# main_module.net
KiCad netlist of a schematic drawn in EAGLE
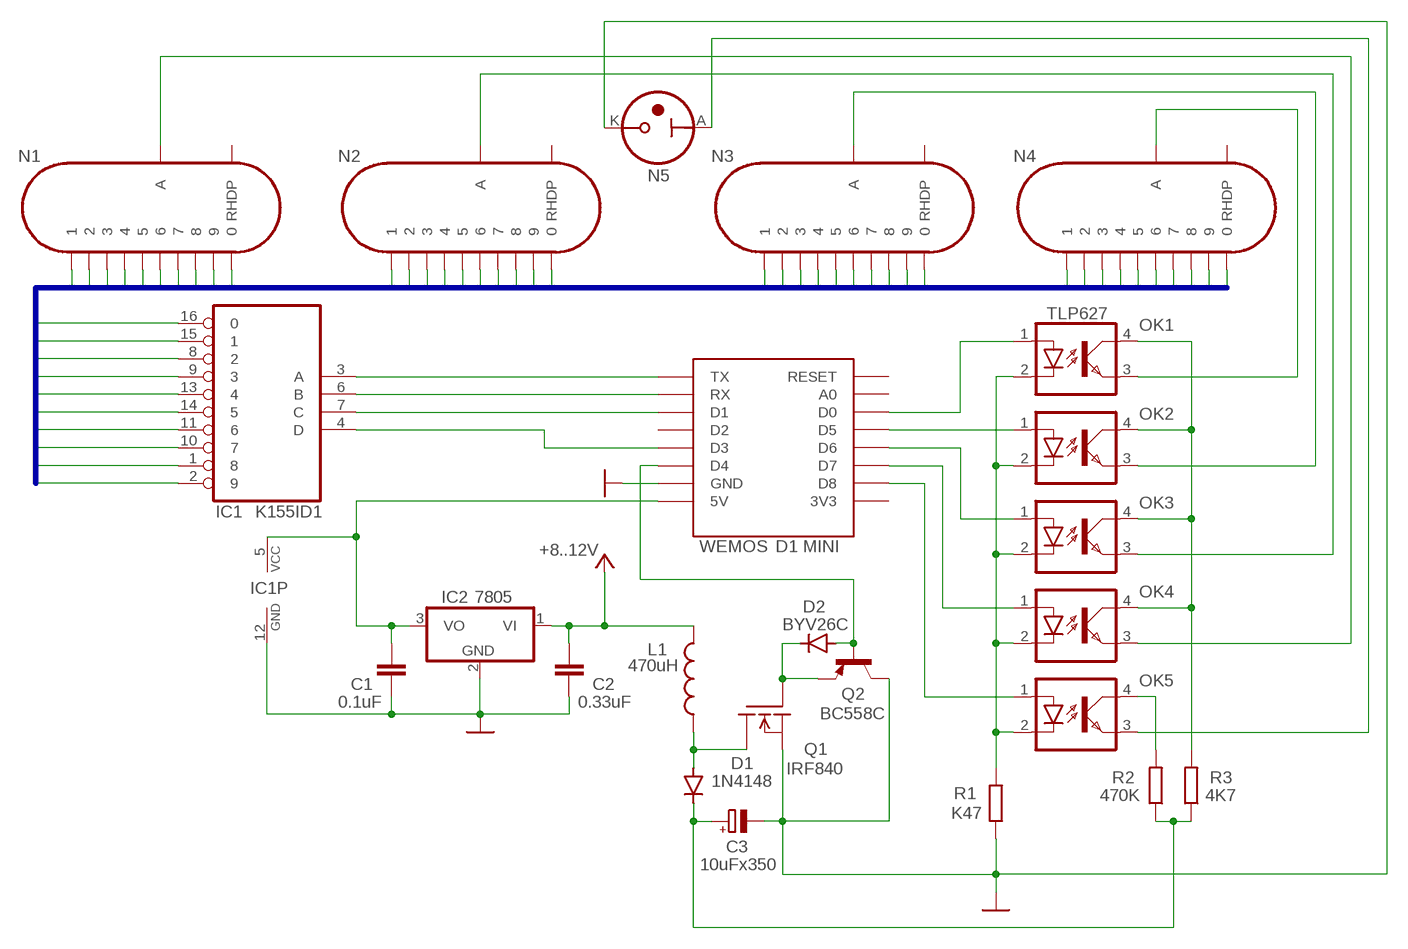
[diagram p0: schematic, sheet 1]

(export (version "E")
  (design (tool "Eeschema 10.0.6"))
  (components
    (comp (ref "C1")
      (value "0.1uF")
      (footprint "eagle-import:C075-052X106")
      (libsource (lib "eagle-import") (part "C-EU075-052X106"))
    )
    (comp (ref "C2")
      (value "0.33uF")
      (footprint "eagle-import:C075-052X106")
      (libsource (lib "eagle-import") (part "C-EU075-052X106"))
    )
    (comp (ref "C3")
      (value "10uFx350")
      (footprint "eagle-import:E5-10,5")
      (libsource (lib "eagle-import") (part "CPOL-EUE5-10.5"))
    )
    (comp (ref "D1")
      (value "1N4148")
      (footprint "eagle-import:DO35-10")
      (libsource (lib "eagle-import") (part "1N4148DO35-10"))
    )
    (comp (ref "D2")
      (value "BYV26C")
      (footprint "eagle-import:SOD57-10")
      (libsource (lib "eagle-import") (part "BYV27"))
    )
    (comp (ref "IC1")
      (value "K155ID1")
      (footprint "eagle-import:DIL16")
      (libsource (lib "eagle-import") (part "74141N"))
    )
    (comp (ref "IC2")
      (value "7805")
      (footprint "eagle-import:TO220H")
      (libsource (lib "eagle-import") (part "78T05"))
    )
    (comp (ref "L1")
      (value "470uH")
      (footprint "eagle-import:6000-XXXX-RC")
      (libsource (lib "eagle-import") (part "L-US6000-XXX-RC"))
    )
    (comp (ref "N1")
      (value "IN-8-2")
      (footprint "eagle-import:IN-8-2")
      (libsource (lib "eagle-import") (part "IN-8-2"))
    )
    (comp (ref "N2")
      (value "IN-8-2")
      (footprint "eagle-import:IN-8-2")
      (libsource (lib "eagle-import") (part "IN-8-2"))
    )
    (comp (ref "N3")
      (value "IN-8-2")
      (footprint "eagle-import:IN-8-2")
      (libsource (lib "eagle-import") (part "IN-8-2"))
    )
    (comp (ref "N4")
      (value "IN-8-2")
      (footprint "eagle-import:IN-8-2")
      (libsource (lib "eagle-import") (part "IN-8-2"))
    )
    (comp (ref "N5")
      (value "IN-3")
      (footprint "eagle-import:IN-3")
      (libsource (lib "eagle-import") (part "IN-3"))
    )
    (comp (ref "OK1")
      (value "TLP627")
      (footprint "eagle-import:DIL04")
      (libsource (lib "eagle-import") (part "LTV816"))
    )
    (comp (ref "OK2")
      (value "LTV816")
      (footprint "eagle-import:DIL04")
      (libsource (lib "eagle-import") (part "LTV816"))
    )
    (comp (ref "OK3")
      (value "LTV816")
      (footprint "eagle-import:DIL04")
      (libsource (lib "eagle-import") (part "LTV816"))
    )
    (comp (ref "OK4")
      (value "LTV816")
      (footprint "eagle-import:DIL04")
      (libsource (lib "eagle-import") (part "LTV816"))
    )
    (comp (ref "OK5")
      (value "LTV816")
      (footprint "eagle-import:DIL04")
      (libsource (lib "eagle-import") (part "LTV816"))
    )
    (comp (ref "Q1")
      (value "IRF840")
      (footprint "eagle-import:TO220")
      (libsource (lib "eagle-import") (part "IRF840"))
    )
    (comp (ref "Q2")
      (value "BC558C")
      (footprint "eagle-import:TO92-EBC")
      (libsource (lib "eagle-import") (part "BC558C"))
    )
    (comp (ref "R1")
      (value "K47")
      (footprint "eagle-import:0207_12")
      (libsource (lib "eagle-import") (part "R-EU_0207/12"))
    )
    (comp (ref "R2")
      (value "470K")
      (footprint "eagle-import:0207_12")
      (libsource (lib "eagle-import") (part "R-EU_0207/12"))
    )
    (comp (ref "R3")
      (value "4K7")
      (footprint "eagle-import:0207_12")
      (libsource (lib "eagle-import") (part "R-EU_0207/12"))
    )
    (comp (ref "WEMOS")
      (value "D1 MINI")
      (footprint "eagle-import:WEMOS-D1-MINI")
      (libsource (lib "eagle-import") (part "WEMOS-D1-MINI"))
    )
  )
  (nets
    (net (code "1") (name "+8..12V") (class "Default")
      (node (ref "C2") (pin "1") (pinfunction "1_1") (pintype "passive"))
      (node (ref "IC2") (pin "1") (pinfunction "VI_1") (pintype "input"))
      (node (ref "L1") (pin "2") (pinfunction "2_2") (pintype "passive"))
    )
    (net (code "2") (name "/N0") (class "Default")
      (node (ref "IC1") (pin "16") (pinfunction "0_16") (pintype "open_collector"))
      (node (ref "N1") (pin "0") (pinfunction "0_0") (pintype "bidirectional"))
      (node (ref "N2") (pin "0") (pinfunction "0_0") (pintype "bidirectional"))
      (node (ref "N3") (pin "0") (pinfunction "0_0") (pintype "bidirectional"))
      (node (ref "N4") (pin "0") (pinfunction "0_0") (pintype "bidirectional"))
    )
    (net (code "3") (name "/N1") (class "Default")
      (node (ref "IC1") (pin "15") (pinfunction "1_15") (pintype "open_collector"))
      (node (ref "N1") (pin "1") (pinfunction "1_1") (pintype "bidirectional"))
      (node (ref "N2") (pin "1") (pinfunction "1_1") (pintype "bidirectional"))
      (node (ref "N3") (pin "1") (pinfunction "1_1") (pintype "bidirectional"))
      (node (ref "N4") (pin "1") (pinfunction "1_1") (pintype "bidirectional"))
    )
    (net (code "4") (name "/N2") (class "Default")
      (node (ref "IC1") (pin "8") (pinfunction "2_8") (pintype "open_collector"))
      (node (ref "N1") (pin "2") (pinfunction "2_2") (pintype "bidirectional"))
      (node (ref "N2") (pin "2") (pinfunction "2_2") (pintype "bidirectional"))
      (node (ref "N3") (pin "2") (pinfunction "2_2") (pintype "bidirectional"))
      (node (ref "N4") (pin "2") (pinfunction "2_2") (pintype "bidirectional"))
    )
    (net (code "5") (name "/N3") (class "Default")
      (node (ref "IC1") (pin "9") (pinfunction "3_9") (pintype "open_collector"))
      (node (ref "N1") (pin "3") (pinfunction "3_3") (pintype "bidirectional"))
      (node (ref "N2") (pin "3") (pinfunction "3_3") (pintype "bidirectional"))
      (node (ref "N3") (pin "3") (pinfunction "3_3") (pintype "bidirectional"))
      (node (ref "N4") (pin "3") (pinfunction "3_3") (pintype "bidirectional"))
    )
    (net (code "6") (name "/N4") (class "Default")
      (node (ref "IC1") (pin "13") (pinfunction "4_13") (pintype "open_collector"))
      (node (ref "N1") (pin "4") (pinfunction "4_4") (pintype "bidirectional"))
      (node (ref "N2") (pin "4") (pinfunction "4_4") (pintype "bidirectional"))
      (node (ref "N3") (pin "4") (pinfunction "4_4") (pintype "bidirectional"))
      (node (ref "N4") (pin "4") (pinfunction "4_4") (pintype "bidirectional"))
    )
    (net (code "7") (name "/N5") (class "Default")
      (node (ref "IC1") (pin "14") (pinfunction "5_14") (pintype "open_collector"))
      (node (ref "N1") (pin "5") (pinfunction "5_5") (pintype "bidirectional"))
      (node (ref "N2") (pin "5") (pinfunction "5_5") (pintype "bidirectional"))
      (node (ref "N3") (pin "5") (pinfunction "5_5") (pintype "bidirectional"))
      (node (ref "N4") (pin "5") (pinfunction "5_5") (pintype "bidirectional"))
    )
    (net (code "8") (name "/N6") (class "Default")
      (node (ref "IC1") (pin "11") (pinfunction "6_11") (pintype "open_collector"))
      (node (ref "N1") (pin "6") (pinfunction "6_6") (pintype "bidirectional"))
      (node (ref "N2") (pin "6") (pinfunction "6_6") (pintype "bidirectional"))
      (node (ref "N3") (pin "6") (pinfunction "6_6") (pintype "bidirectional"))
      (node (ref "N4") (pin "6") (pinfunction "6_6") (pintype "bidirectional"))
    )
    (net (code "9") (name "/N7") (class "Default")
      (node (ref "IC1") (pin "10") (pinfunction "7_10") (pintype "open_collector"))
      (node (ref "N1") (pin "7") (pinfunction "7_7") (pintype "bidirectional"))
      (node (ref "N2") (pin "7") (pinfunction "7_7") (pintype "bidirectional"))
      (node (ref "N3") (pin "7") (pinfunction "7_7") (pintype "bidirectional"))
      (node (ref "N4") (pin "7") (pinfunction "7_7") (pintype "bidirectional"))
    )
    (net (code "10") (name "/N8") (class "Default")
      (node (ref "IC1") (pin "1") (pinfunction "8_1") (pintype "open_collector"))
      (node (ref "N1") (pin "8") (pinfunction "8_8") (pintype "bidirectional"))
      (node (ref "N2") (pin "8") (pinfunction "8_8") (pintype "bidirectional"))
      (node (ref "N3") (pin "8") (pinfunction "8_8") (pintype "bidirectional"))
      (node (ref "N4") (pin "8") (pinfunction "8_8") (pintype "bidirectional"))
    )
    (net (code "11") (name "/N9") (class "Default")
      (node (ref "IC1") (pin "2") (pinfunction "9_2") (pintype "open_collector"))
      (node (ref "N1") (pin "9") (pinfunction "9_9") (pintype "bidirectional"))
      (node (ref "N2") (pin "9") (pinfunction "9_9") (pintype "bidirectional"))
      (node (ref "N3") (pin "9") (pinfunction "9_9") (pintype "bidirectional"))
      (node (ref "N4") (pin "9") (pinfunction "9_9") (pintype "bidirectional"))
    )
    (net (code "12") (name "GND") (class "Default")
      (node (ref "C1") (pin "2") (pinfunction "2_2") (pintype "passive"))
      (node (ref "C2") (pin "2") (pinfunction "2_2") (pintype "passive"))
      (node (ref "C3") (pin "-") (pinfunction "-_-") (pintype "passive"))
      (node (ref "IC1") (pin "12") (pinfunction "GND_12") (pintype "power_in"))
      (node (ref "IC2") (pin "2") (pinfunction "GND_2") (pintype "passive"))
      (node (ref "N5") (pin "K") (pinfunction "K_K") (pintype "bidirectional"))
      (node (ref "Q1") (pin "3") (pinfunction "S_3") (pintype "passive"))
      (node (ref "Q2") (pin "C") (pinfunction "C_C") (pintype "passive"))
      (node (ref "R1") (pin "1") (pinfunction "1_1") (pintype "passive"))
      (node (ref "WEMOS") (pin "GND") (pinfunction "GND_GND") (pintype "bidirectional"))
    )
    (net (code "13") (name "Net-(C3-Pad+)") (class "Default")
      (node (ref "C3") (pin "+") (pinfunction "+_+") (pintype "passive"))
      (node (ref "D1") (pin "C") (pinfunction "C_C") (pintype "passive"))
      (node (ref "R2") (pin "1") (pinfunction "1_1") (pintype "passive"))
      (node (ref "R3") (pin "1") (pinfunction "1_1") (pintype "passive"))
    )
    (net (code "14") (name "Net-(D2-PadA)") (class "Default")
      (node (ref "D2") (pin "A") (pinfunction "A_A") (pintype "passive"))
      (node (ref "Q2") (pin "B") (pinfunction "B_B") (pintype "passive"))
      (node (ref "WEMOS") (pin "D4") (pinfunction "D4_D4") (pintype "bidirectional"))
    )
    (net (code "15") (name "Net-(IC1A-A)") (class "Default")
      (node (ref "IC1") (pin "3") (pinfunction "A_3") (pintype "input"))
      (node (ref "WEMOS") (pin "TX") (pinfunction "TX_TX") (pintype "bidirectional"))
    )
    (net (code "16") (name "Net-(IC1A-B)") (class "Default")
      (node (ref "IC1") (pin "6") (pinfunction "B_6") (pintype "input"))
      (node (ref "WEMOS") (pin "RX") (pinfunction "RX_RX") (pintype "bidirectional"))
    )
    (net (code "17") (name "Net-(IC1A-C)") (class "Default")
      (node (ref "IC1") (pin "7") (pinfunction "C_7") (pintype "input"))
      (node (ref "WEMOS") (pin "D1") (pinfunction "D1_D1") (pintype "bidirectional"))
    )
    (net (code "18") (name "Net-(IC1A-D)") (class "Default")
      (node (ref "IC1") (pin "4") (pinfunction "D_4") (pintype "input"))
      (node (ref "WEMOS") (pin "D3") (pinfunction "D3_D3") (pintype "bidirectional"))
    )
    (net (code "19") (name "Net-(IC1B-VCC)") (class "Default")
      (node (ref "C1") (pin "1") (pinfunction "1_1") (pintype "passive"))
      (node (ref "IC1") (pin "5") (pinfunction "VCC_5") (pintype "power_in"))
      (node (ref "IC2") (pin "3") (pinfunction "VO_3") (pintype "passive"))
      (node (ref "WEMOS") (pin "5V") (pinfunction "5V_5V") (pintype "bidirectional"))
    )
    (net (code "20") (name "Net-(OK1-A)") (class "Default")
      (node (ref "OK1") (pin "1") (pinfunction "A_1") (pintype "passive"))
      (node (ref "WEMOS") (pin "D0") (pinfunction "D0_D0") (pintype "bidirectional"))
    )
    (net (code "21") (name "Net-(OK1-C)") (class "Default")
      (node (ref "OK1") (pin "2") (pinfunction "C_2") (pintype "passive"))
      (node (ref "OK2") (pin "2") (pinfunction "C_2") (pintype "passive"))
      (node (ref "OK3") (pin "2") (pinfunction "C_2") (pintype "passive"))
      (node (ref "OK4") (pin "2") (pinfunction "C_2") (pintype "passive"))
      (node (ref "OK5") (pin "2") (pinfunction "C_2") (pintype "passive"))
      (node (ref "R1") (pin "2") (pinfunction "2_2") (pintype "passive"))
    )
    (net (code "22") (name "Net-(OK1-COL)") (class "Default")
      (node (ref "OK1") (pin "4") (pinfunction "COL_4") (pintype "passive"))
      (node (ref "OK2") (pin "4") (pinfunction "COL_4") (pintype "passive"))
      (node (ref "OK3") (pin "4") (pinfunction "COL_4") (pintype "passive"))
      (node (ref "OK4") (pin "4") (pinfunction "COL_4") (pintype "passive"))
      (node (ref "R3") (pin "2") (pinfunction "2_2") (pintype "passive"))
    )
    (net (code "23") (name "Net-(OK1-EMIT)") (class "Default")
      (node (ref "N4") (pin "A") (pinfunction "A_A") (pintype "bidirectional"))
      (node (ref "OK1") (pin "3") (pinfunction "EMIT_3") (pintype "passive"))
    )
    (net (code "24") (name "Net-(OK2-A)") (class "Default")
      (node (ref "OK2") (pin "1") (pinfunction "A_1") (pintype "passive"))
      (node (ref "WEMOS") (pin "D5") (pinfunction "D5_D5") (pintype "bidirectional"))
    )
    (net (code "25") (name "Net-(OK2-EMIT)") (class "Default")
      (node (ref "N3") (pin "A") (pinfunction "A_A") (pintype "bidirectional"))
      (node (ref "OK2") (pin "3") (pinfunction "EMIT_3") (pintype "passive"))
    )
    (net (code "26") (name "Net-(OK3-A)") (class "Default")
      (node (ref "OK3") (pin "1") (pinfunction "A_1") (pintype "passive"))
      (node (ref "WEMOS") (pin "D6") (pinfunction "D6_D6") (pintype "bidirectional"))
    )
    (net (code "27") (name "Net-(OK3-EMIT)") (class "Default")
      (node (ref "N2") (pin "A") (pinfunction "A_A") (pintype "bidirectional"))
      (node (ref "OK3") (pin "3") (pinfunction "EMIT_3") (pintype "passive"))
    )
    (net (code "28") (name "Net-(OK4-A)") (class "Default")
      (node (ref "OK4") (pin "1") (pinfunction "A_1") (pintype "passive"))
      (node (ref "WEMOS") (pin "D7") (pinfunction "D7_D7") (pintype "bidirectional"))
    )
    (net (code "29") (name "Net-(OK4-EMIT)") (class "Default")
      (node (ref "N1") (pin "A") (pinfunction "A_A") (pintype "bidirectional"))
      (node (ref "OK4") (pin "3") (pinfunction "EMIT_3") (pintype "passive"))
    )
    (net (code "30") (name "Net-(OK5-A)") (class "Default")
      (node (ref "OK5") (pin "1") (pinfunction "A_1") (pintype "passive"))
      (node (ref "WEMOS") (pin "D8") (pinfunction "D8_D8") (pintype "bidirectional"))
    )
    (net (code "31") (name "Net-(OK5-COL)") (class "Default")
      (node (ref "OK5") (pin "4") (pinfunction "COL_4") (pintype "passive"))
      (node (ref "R2") (pin "2") (pinfunction "2_2") (pintype "passive"))
    )
    (net (code "32") (name "Net-(OK5-EMIT)") (class "Default")
      (node (ref "N5") (pin "A") (pinfunction "A_A") (pintype "bidirectional"))
      (node (ref "OK5") (pin "3") (pinfunction "EMIT_3") (pintype "passive"))
    )
    (net (code "33") (name "Net-(Q1-D)") (class "Default")
      (node (ref "D1") (pin "A") (pinfunction "A_A") (pintype "passive"))
      (node (ref "L1") (pin "1") (pinfunction "1_1") (pintype "passive"))
      (node (ref "Q1") (pin "2") (pinfunction "D_2") (pintype "passive"))
    )
    (net (code "34") (name "Net-(Q1-G)") (class "Default")
      (node (ref "D2") (pin "C") (pinfunction "C_C") (pintype "passive"))
      (node (ref "Q1") (pin "1") (pinfunction "G_1") (pintype "passive"))
      (node (ref "Q2") (pin "E") (pinfunction "E_E") (pintype "passive"))
    )
    (net (code "35") (name "unconnected-(N1-RHDP-Pad.)") (class "Default")
      (node (ref "N1") (pin ".") (pinfunction "RHDP_.") (pintype "bidirectional"))
    )
    (net (code "36") (name "unconnected-(N2-RHDP-Pad.)") (class "Default")
      (node (ref "N2") (pin ".") (pinfunction "RHDP_.") (pintype "bidirectional"))
    )
    (net (code "37") (name "unconnected-(N3-RHDP-Pad.)") (class "Default")
      (node (ref "N3") (pin ".") (pinfunction "RHDP_.") (pintype "bidirectional"))
    )
    (net (code "38") (name "unconnected-(N4-RHDP-Pad.)") (class "Default")
      (node (ref "N4") (pin ".") (pinfunction "RHDP_.") (pintype "bidirectional"))
    )
    (net (code "39") (name "unconnected-(WEMOS-Pad3V3)") (class "Default")
      (node (ref "WEMOS") (pin "3V3") (pinfunction "3V3_3V3") (pintype "bidirectional"))
    )
    (net (code "40") (name "unconnected-(WEMOS-PadA0)") (class "Default")
      (node (ref "WEMOS") (pin "A0") (pinfunction "A0_A0") (pintype "bidirectional"))
    )
    (net (code "41") (name "unconnected-(WEMOS-PadD2)") (class "Default")
      (node (ref "WEMOS") (pin "D2") (pinfunction "D2_D2") (pintype "bidirectional"))
    )
    (net (code "42") (name "unconnected-(WEMOS-PadRESET)") (class "Default")
      (node (ref "WEMOS") (pin "RESET") (pinfunction "RESET_RESET") (pintype "bidirectional"))
    )
  )
)
